# atmegademo.net
KiCad netlist of a schematic drawn in EAGLE
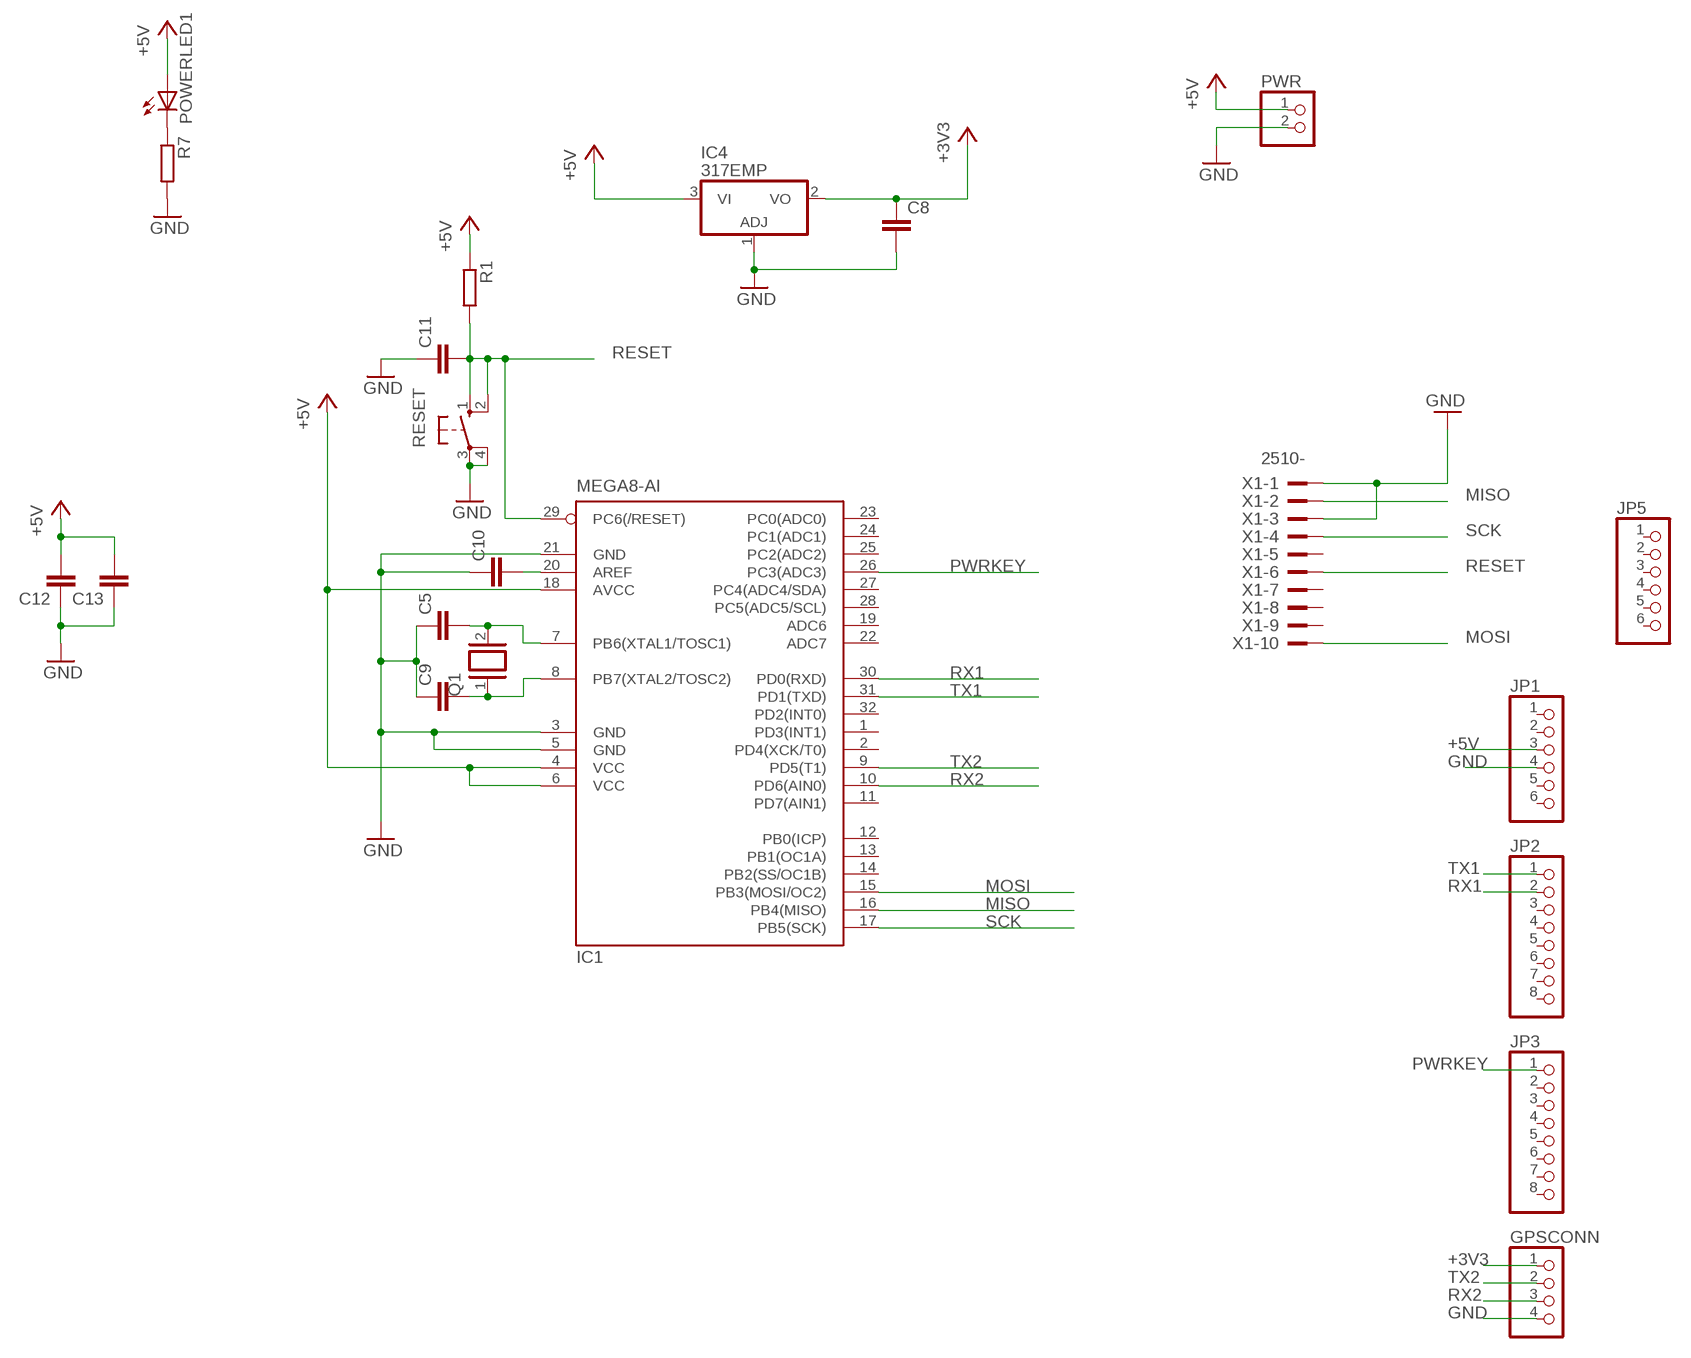
[diagram p0: schematic, sheet 1]

(export (version "E")
  (design (tool "Eeschema 10.0.6"))
  (components
    (comp (ref "C5")
      (value "C-EUC0805K")
      (footprint "eagle-import:C0805K")
      (libsource (lib "eagle-import") (part "C-EUC0805K"))
    )
    (comp (ref "C8")
      (value "C-EUC0805K")
      (footprint "eagle-import:C0805K")
      (libsource (lib "eagle-import") (part "C-EUC0805K"))
    )
    (comp (ref "C9")
      (value "C-EUC0805K")
      (footprint "eagle-import:C0805K")
      (libsource (lib "eagle-import") (part "C-EUC0805K"))
    )
    (comp (ref "C10")
      (value "C-EUC0805K")
      (footprint "eagle-import:C0805K")
      (libsource (lib "eagle-import") (part "C-EUC0805K"))
    )
    (comp (ref "C11")
      (value "C-EUC0805K")
      (footprint "eagle-import:C0805K")
      (libsource (lib "eagle-import") (part "C-EUC0805K"))
    )
    (comp (ref "C12")
      (value "C-EUC0805K")
      (footprint "eagle-import:C0805K")
      (libsource (lib "eagle-import") (part "C-EUC0805K"))
    )
    (comp (ref "C13")
      (value "C-EUC0805K")
      (footprint "eagle-import:C0805K")
      (libsource (lib "eagle-import") (part "C-EUC0805K"))
    )
    (comp (ref "GPSCONN")
      (value "PINHD-1X4")
      (footprint "eagle-import:1X04")
      (libsource (lib "eagle-import") (part "PINHD-1X4"))
    )
    (comp (ref "IC1")
      (value "MEGA8-AI")
      (footprint "eagle-import:TQFP32-08")
      (fields (field (name "MPN") "ATMEGA8-16AU"))
      (libsource (lib "eagle-import") (part "MEGA8-AI"))
    )
    (comp (ref "IC4")
      (value "317EMP")
      (footprint "eagle-import:SOT223")
      (libsource (lib "eagle-import") (part "317EMP"))
    )
    (comp (ref "JP1")
      (value "PINHD-1X6CLEAN")
      (footprint "eagle-import:1X06-CLEAN")
      (libsource (lib "eagle-import") (part "PINHD-1X6CLEAN"))
    )
    (comp (ref "JP2")
      (value "PINHD-1X8CLEANBIG")
      (footprint "eagle-import:1X08-CLEANBIG")
      (libsource (lib "eagle-import") (part "PINHD-1X8CLEANBIG"))
    )
    (comp (ref "JP3")
      (value "PINHD-1X8CLEANBIG")
      (footprint "eagle-import:1X08-CLEANBIG")
      (libsource (lib "eagle-import") (part "PINHD-1X8CLEANBIG"))
    )
    (comp (ref "JP5")
      (value "PINHD-1X6CLEAN")
      (footprint "eagle-import:1X06-CLEAN")
      (libsource (lib "eagle-import") (part "PINHD-1X6CLEAN"))
    )
    (comp (ref "POWERLED1")
      (value "LEDCHIP-LED0805")
      (footprint "eagle-import:CHIP-LED0805")
      (libsource (lib "eagle-import") (part "LEDCHIP-LED0805"))
    )
    (comp (ref "PWR")
      (value "PINHD-1X2")
      (footprint "eagle-import:1X02")
      (libsource (lib "eagle-import") (part "PINHD-1X2"))
    )
    (comp (ref "Q1")
      (value "XTAL/S")
      (footprint "eagle-import:QS")
      (libsource (lib "eagle-import") (part "XTAL/S"))
    )
    (comp (ref "R1")
      (value "R-EU_R0805")
      (footprint "eagle-import:R0805")
      (libsource (lib "eagle-import") (part "R-EU_R0805"))
    )
    (comp (ref "R7")
      (value "R-EU_R0805")
      (footprint "eagle-import:R0805")
      (libsource (lib "eagle-import") (part "R-EU_R0805"))
    )
    (comp (ref "RESET")
      (value "10-XX")
      (footprint "eagle-import:B3F-10XX")
      (fields (field (name "MPN") "B3F-1000"))
      (libsource (lib "eagle-import") (part "10-XX"))
    )
    (comp (ref "X1")
      (value "2510-")
      (footprint "eagle-import:PAK100_2500-10")
      (fields (field (name "MF") "3M") (field (name "MPN") "2510-6002UB"))
      (libsource (lib "eagle-import") (part "2510-"))
    )
  )
  (nets
    (net (code "1") (name "+3V3") (class "Default")
      (node (ref "C8") (pin "1") (pinfunction "1_1") (pintype "passive"))
      (node (ref "GPSCONN") (pin "1") (pinfunction "1_1") (pintype "passive"))
      (node (ref "IC4") (pin "2") (pinfunction "VO_2") (pintype "passive"))
    )
    (net (code "2") (name "+5V") (class "Default")
      (node (ref "C12") (pin "2") (pinfunction "2_2") (pintype "passive"))
      (node (ref "C13") (pin "2") (pinfunction "2_2") (pintype "passive"))
      (node (ref "IC1") (pin "18") (pinfunction "AVCC_18") (pintype "power_in"))
      (node (ref "IC1") (pin "4") (pinfunction "VCC_4") (pintype "power_in"))
      (node (ref "IC1") (pin "6") (pinfunction "VCC_6") (pintype "power_in"))
      (node (ref "IC4") (pin "3") (pinfunction "VI_3") (pintype "input"))
      (node (ref "JP1") (pin "3") (pinfunction "3_3") (pintype "passive"))
      (node (ref "POWERLED1") (pin "A") (pinfunction "A_A") (pintype "passive"))
      (node (ref "PWR") (pin "1") (pinfunction "1_1") (pintype "passive"))
      (node (ref "R1") (pin "1") (pinfunction "1_1") (pintype "passive"))
    )
    (net (code "3") (name "/MISO") (class "Default")
      (node (ref "IC1") (pin "16") (pinfunction "PB4(MISO)_16") (pintype "bidirectional"))
      (node (ref "X1") (pin "2") (pinfunction "KL_2") (pintype "passive"))
    )
    (net (code "4") (name "/MOSI") (class "Default")
      (node (ref "IC1") (pin "15") (pinfunction "PB3(MOSI/OC2)_15") (pintype "bidirectional"))
      (node (ref "X1") (pin "10") (pinfunction "KL_10") (pintype "passive"))
    )
    (net (code "5") (name "/PWRKEY") (class "Default")
      (node (ref "IC1") (pin "26") (pinfunction "PC3(ADC3)_26") (pintype "bidirectional"))
      (node (ref "JP3") (pin "1") (pinfunction "1_1") (pintype "passive"))
    )
    (net (code "6") (name "/RESET") (class "Default")
      (node (ref "C11") (pin "2") (pinfunction "2_2") (pintype "passive"))
      (node (ref "IC1") (pin "29") (pinfunction "PC6(/RESET)_29") (pintype "bidirectional"))
      (node (ref "R1") (pin "2") (pinfunction "2_2") (pintype "passive"))
      (node (ref "RESET") (pin "1") (pinfunction "S_1") (pintype "passive"))
      (node (ref "RESET") (pin "2") (pinfunction "S1_2") (pintype "passive"))
      (node (ref "X1") (pin "6") (pinfunction "KL_6") (pintype "passive"))
    )
    (net (code "7") (name "/RX1") (class "Default")
      (node (ref "IC1") (pin "30") (pinfunction "PD0(RXD)_30") (pintype "bidirectional"))
      (node (ref "JP2") (pin "2") (pinfunction "2_2") (pintype "passive"))
    )
    (net (code "8") (name "/RX2") (class "Default")
      (node (ref "GPSCONN") (pin "3") (pinfunction "3_3") (pintype "passive"))
      (node (ref "IC1") (pin "10") (pinfunction "PD6(AIN0)_10") (pintype "bidirectional"))
    )
    (net (code "9") (name "/SCK") (class "Default")
      (node (ref "IC1") (pin "17") (pinfunction "PB5(SCK)_17") (pintype "bidirectional"))
      (node (ref "X1") (pin "4") (pinfunction "KL_4") (pintype "passive"))
    )
    (net (code "10") (name "/TX1") (class "Default")
      (node (ref "IC1") (pin "31") (pinfunction "PD1(TXD)_31") (pintype "bidirectional"))
      (node (ref "JP2") (pin "1") (pinfunction "1_1") (pintype "passive"))
    )
    (net (code "11") (name "/TX2") (class "Default")
      (node (ref "GPSCONN") (pin "2") (pinfunction "2_2") (pintype "passive"))
      (node (ref "IC1") (pin "9") (pinfunction "PD5(T1)_9") (pintype "bidirectional"))
    )
    (net (code "12") (name "GND") (class "Default")
      (node (ref "C10") (pin "1") (pinfunction "1_1") (pintype "passive"))
      (node (ref "C11") (pin "1") (pinfunction "1_1") (pintype "passive"))
      (node (ref "C12") (pin "1") (pinfunction "1_1") (pintype "passive"))
      (node (ref "C13") (pin "1") (pinfunction "1_1") (pintype "passive"))
      (node (ref "C5") (pin "1") (pinfunction "1_1") (pintype "passive"))
      (node (ref "C8") (pin "2") (pinfunction "2_2") (pintype "passive"))
      (node (ref "C9") (pin "1") (pinfunction "1_1") (pintype "passive"))
      (node (ref "GPSCONN") (pin "4") (pinfunction "4_4") (pintype "passive"))
      (node (ref "IC1") (pin "21") (pinfunction "GND_21") (pintype "power_in"))
      (node (ref "IC1") (pin "3") (pinfunction "GND_3") (pintype "power_in"))
      (node (ref "IC1") (pin "5") (pinfunction "GND_5") (pintype "power_in"))
      (node (ref "IC4") (pin "1") (pinfunction "ADJ_1") (pintype "input"))
      (node (ref "JP1") (pin "4") (pinfunction "4_4") (pintype "passive"))
      (node (ref "PWR") (pin "2") (pinfunction "2_2") (pintype "passive"))
      (node (ref "R7") (pin "2") (pinfunction "2_2") (pintype "passive"))
      (node (ref "RESET") (pin "3") (pinfunction "P_3") (pintype "passive"))
      (node (ref "RESET") (pin "4") (pinfunction "P1_4") (pintype "passive"))
      (node (ref "X1") (pin "1") (pinfunction "KL_1") (pintype "passive"))
      (node (ref "X1") (pin "3") (pinfunction "KL_3") (pintype "passive"))
    )
    (net (code "13") (name "Net-(IC1-AREF)") (class "Default")
      (node (ref "C10") (pin "2") (pinfunction "2_2") (pintype "passive"))
      (node (ref "IC1") (pin "20") (pinfunction "AREF_20") (pintype "passive"))
    )
    (net (code "14") (name "Net-(IC1-PB6(XTAL1{slash}TOSC1))") (class "Default")
      (node (ref "C5") (pin "2") (pinfunction "2_2") (pintype "passive"))
      (node (ref "IC1") (pin "7") (pinfunction "PB6(XTAL1/TOSC1)_7") (pintype "bidirectional"))
      (node (ref "Q1") (pin "2") (pinfunction "2_2") (pintype "passive"))
    )
    (net (code "15") (name "Net-(IC1-PB7(XTAL2{slash}TOSC2))") (class "Default")
      (node (ref "C9") (pin "2") (pinfunction "2_2") (pintype "passive"))
      (node (ref "IC1") (pin "8") (pinfunction "PB7(XTAL2/TOSC2)_8") (pintype "bidirectional"))
      (node (ref "Q1") (pin "1") (pinfunction "1_1") (pintype "passive"))
    )
    (net (code "16") (name "Net-(POWERLED1-PadC)") (class "Default")
      (node (ref "POWERLED1") (pin "C") (pinfunction "C_C") (pintype "passive"))
      (node (ref "R7") (pin "1") (pinfunction "1_1") (pintype "passive"))
    )
    (net (code "17") (name "unconnected-(IC1-ADC6-Pad19)") (class "Default")
      (node (ref "IC1") (pin "19") (pinfunction "ADC6_19") (pintype "bidirectional"))
    )
    (net (code "18") (name "unconnected-(IC1-ADC7-Pad22)") (class "Default")
      (node (ref "IC1") (pin "22") (pinfunction "ADC7_22") (pintype "bidirectional"))
    )
    (net (code "19") (name "unconnected-(IC1-PB0(ICP)-Pad12)") (class "Default")
      (node (ref "IC1") (pin "12") (pinfunction "PB0(ICP)_12") (pintype "bidirectional"))
    )
    (net (code "20") (name "unconnected-(IC1-PB1(OC1A)-Pad13)") (class "Default")
      (node (ref "IC1") (pin "13") (pinfunction "PB1(OC1A)_13") (pintype "bidirectional"))
    )
    (net (code "21") (name "unconnected-(IC1-PB2(SS{slash}OC1B)-Pad14)") (class "Default")
      (node (ref "IC1") (pin "14") (pinfunction "PB2(SS/OC1B)_14") (pintype "bidirectional"))
    )
    (net (code "22") (name "unconnected-(IC1-PC0(ADC0)-Pad23)") (class "Default")
      (node (ref "IC1") (pin "23") (pinfunction "PC0(ADC0)_23") (pintype "bidirectional"))
    )
    (net (code "23") (name "unconnected-(IC1-PC1(ADC1)-Pad24)") (class "Default")
      (node (ref "IC1") (pin "24") (pinfunction "PC1(ADC1)_24") (pintype "bidirectional"))
    )
    (net (code "24") (name "unconnected-(IC1-PC2(ADC2)-Pad25)") (class "Default")
      (node (ref "IC1") (pin "25") (pinfunction "PC2(ADC2)_25") (pintype "bidirectional"))
    )
    (net (code "25") (name "unconnected-(IC1-PC4(ADC4{slash}SDA)-Pad27)") (class "Default")
      (node (ref "IC1") (pin "27") (pinfunction "PC4(ADC4/SDA)_27") (pintype "bidirectional"))
    )
    (net (code "26") (name "unconnected-(IC1-PC5(ADC5{slash}SCL)-Pad28)") (class "Default")
      (node (ref "IC1") (pin "28") (pinfunction "PC5(ADC5/SCL)_28") (pintype "bidirectional"))
    )
    (net (code "27") (name "unconnected-(IC1-PD2(INT0)-Pad32)") (class "Default")
      (node (ref "IC1") (pin "32") (pinfunction "PD2(INT0)_32") (pintype "bidirectional"))
    )
    (net (code "28") (name "unconnected-(IC1-PD3(INT1)-Pad1)") (class "Default")
      (node (ref "IC1") (pin "1") (pinfunction "PD3(INT1)_1") (pintype "bidirectional"))
    )
    (net (code "29") (name "unconnected-(IC1-PD4(XCK{slash}T0)-Pad2)") (class "Default")
      (node (ref "IC1") (pin "2") (pinfunction "PD4(XCK/T0)_2") (pintype "bidirectional"))
    )
    (net (code "30") (name "unconnected-(IC1-PD7(AIN1)-Pad11)") (class "Default")
      (node (ref "IC1") (pin "11") (pinfunction "PD7(AIN1)_11") (pintype "bidirectional"))
    )
    (net (code "31") (name "unconnected-(JP1-Pad1)") (class "Default")
      (node (ref "JP1") (pin "1") (pinfunction "1_1") (pintype "passive"))
    )
    (net (code "32") (name "unconnected-(JP1-Pad2)") (class "Default")
      (node (ref "JP1") (pin "2") (pinfunction "2_2") (pintype "passive"))
    )
    (net (code "33") (name "unconnected-(JP1-Pad5)") (class "Default")
      (node (ref "JP1") (pin "5") (pinfunction "5_5") (pintype "passive"))
    )
    (net (code "34") (name "unconnected-(JP1-Pad6)") (class "Default")
      (node (ref "JP1") (pin "6") (pinfunction "6_6") (pintype "passive"))
    )
    (net (code "35") (name "unconnected-(JP2-Pad3)") (class "Default")
      (node (ref "JP2") (pin "3") (pinfunction "3_3") (pintype "passive"))
    )
    (net (code "36") (name "unconnected-(JP2-Pad4)") (class "Default")
      (node (ref "JP2") (pin "4") (pinfunction "4_4") (pintype "passive"))
    )
    (net (code "37") (name "unconnected-(JP2-Pad5)") (class "Default")
      (node (ref "JP2") (pin "5") (pinfunction "5_5") (pintype "passive"))
    )
    (net (code "38") (name "unconnected-(JP2-Pad6)") (class "Default")
      (node (ref "JP2") (pin "6") (pinfunction "6_6") (pintype "passive"))
    )
    (net (code "39") (name "unconnected-(JP2-Pad7)") (class "Default")
      (node (ref "JP2") (pin "7") (pinfunction "7_7") (pintype "passive"))
    )
    (net (code "40") (name "unconnected-(JP2-Pad8)") (class "Default")
      (node (ref "JP2") (pin "8") (pinfunction "8_8") (pintype "passive"))
    )
    (net (code "41") (name "unconnected-(JP3-Pad2)") (class "Default")
      (node (ref "JP3") (pin "2") (pinfunction "2_2") (pintype "passive"))
    )
    (net (code "42") (name "unconnected-(JP3-Pad3)") (class "Default")
      (node (ref "JP3") (pin "3") (pinfunction "3_3") (pintype "passive"))
    )
    (net (code "43") (name "unconnected-(JP3-Pad4)") (class "Default")
      (node (ref "JP3") (pin "4") (pinfunction "4_4") (pintype "passive"))
    )
    (net (code "44") (name "unconnected-(JP3-Pad5)") (class "Default")
      (node (ref "JP3") (pin "5") (pinfunction "5_5") (pintype "passive"))
    )
    (net (code "45") (name "unconnected-(JP3-Pad6)") (class "Default")
      (node (ref "JP3") (pin "6") (pinfunction "6_6") (pintype "passive"))
    )
    (net (code "46") (name "unconnected-(JP3-Pad7)") (class "Default")
      (node (ref "JP3") (pin "7") (pinfunction "7_7") (pintype "passive"))
    )
    (net (code "47") (name "unconnected-(JP3-Pad8)") (class "Default")
      (node (ref "JP3") (pin "8") (pinfunction "8_8") (pintype "passive"))
    )
    (net (code "48") (name "unconnected-(JP5-Pad1)") (class "Default")
      (node (ref "JP5") (pin "1") (pinfunction "1_1") (pintype "passive"))
    )
    (net (code "49") (name "unconnected-(JP5-Pad2)") (class "Default")
      (node (ref "JP5") (pin "2") (pinfunction "2_2") (pintype "passive"))
    )
    (net (code "50") (name "unconnected-(JP5-Pad3)") (class "Default")
      (node (ref "JP5") (pin "3") (pinfunction "3_3") (pintype "passive"))
    )
    (net (code "51") (name "unconnected-(JP5-Pad4)") (class "Default")
      (node (ref "JP5") (pin "4") (pinfunction "4_4") (pintype "passive"))
    )
    (net (code "52") (name "unconnected-(JP5-Pad5)") (class "Default")
      (node (ref "JP5") (pin "5") (pinfunction "5_5") (pintype "passive"))
    )
    (net (code "53") (name "unconnected-(JP5-Pad6)") (class "Default")
      (node (ref "JP5") (pin "6") (pinfunction "6_6") (pintype "passive"))
    )
    (net (code "54") (name "unconnected-(X1F-KL-Pad5)") (class "Default")
      (node (ref "X1") (pin "5") (pinfunction "KL_5") (pintype "passive"))
    )
    (net (code "55") (name "unconnected-(X1H-KL-Pad7)") (class "Default")
      (node (ref "X1") (pin "7") (pinfunction "KL_7") (pintype "passive"))
    )
    (net (code "56") (name "unconnected-(X1I-KL-Pad8)") (class "Default")
      (node (ref "X1") (pin "8") (pinfunction "KL_8") (pintype "passive"))
    )
    (net (code "57") (name "unconnected-(X1J-KL-Pad9)") (class "Default")
      (node (ref "X1") (pin "9") (pinfunction "KL_9") (pintype "passive"))
    )
  )
)
